# design.net
KiCad netlist of a schematic drawn in Altium Designer
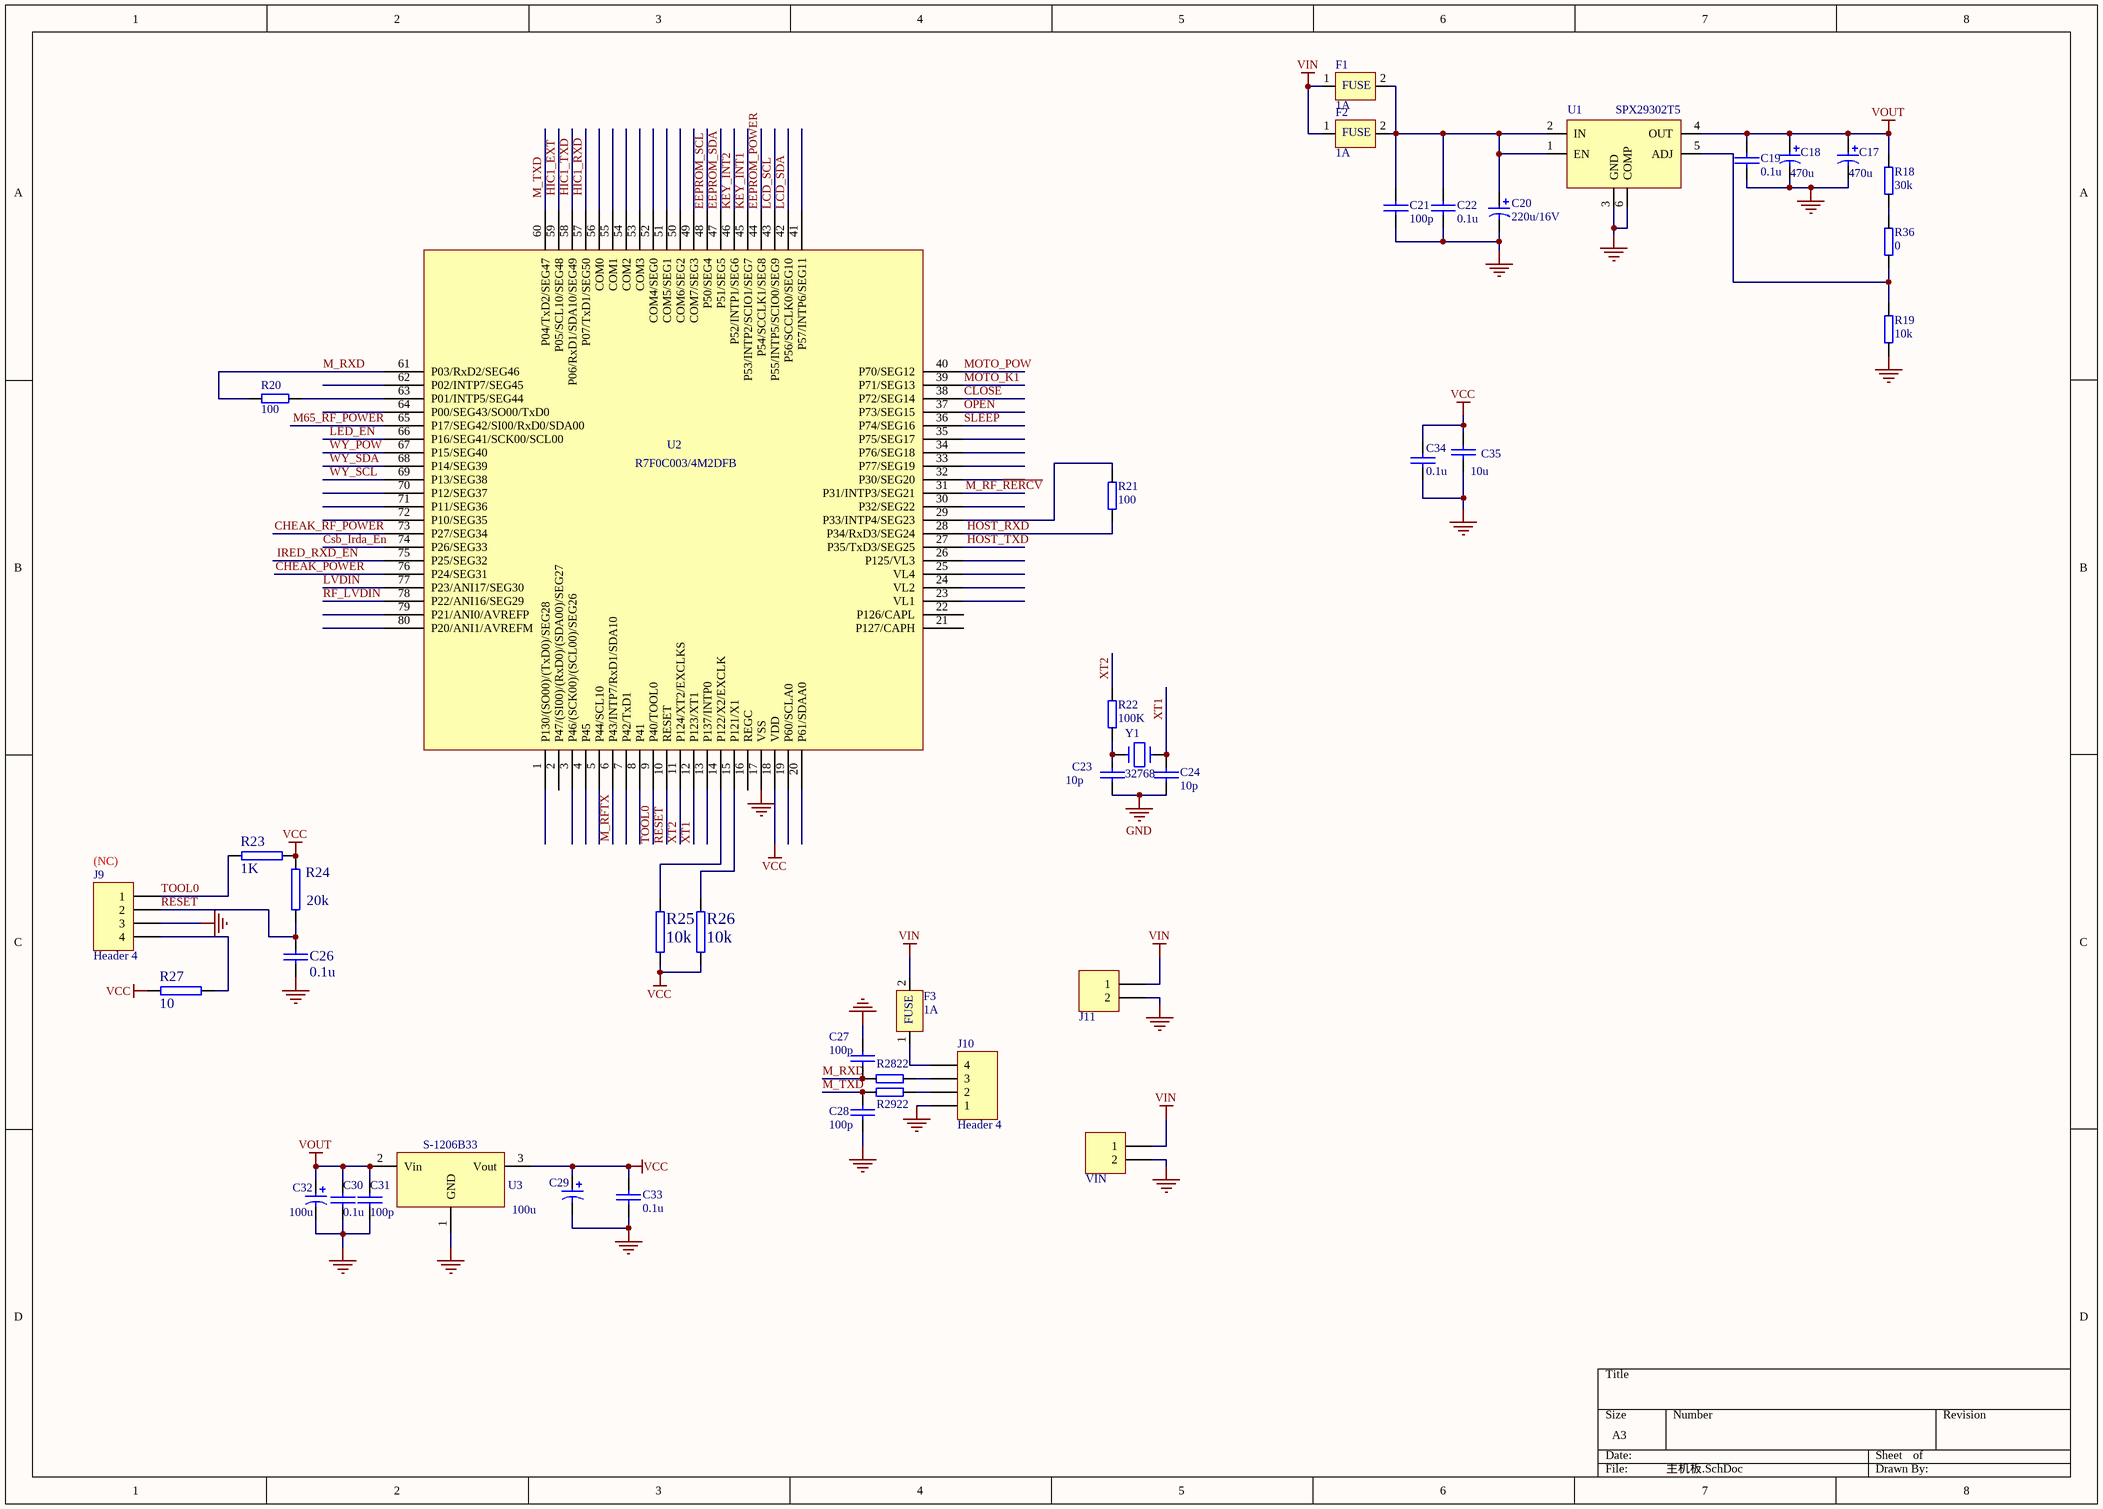
[diagram p0: 主机板.SchDoc]

(export (version "E")
  (design (tool "Eeschema 10.0.6"))
  (components
    (comp (ref "C17")
      (value "470u")
      (footprint "7343")
      (description "钽电容")
      (libsource (lib "CBB_Lib_SCH") (part "CAP-POL2"))
    )
    (comp (ref "C18")
      (value "470u")
      (footprint "7343")
      (description "钽电容")
      (libsource (lib "CBB_Lib_SCH") (part "CAP-POL2"))
    )
    (comp (ref "C19")
      (value "0.1u")
      (footprint "C0603")
      (description "无极性电容")
      (libsource (lib "CBB_Lib_SCH") (part "CAP"))
    )
    (comp (ref "C20")
      (value "220u/16V")
      (footprint "7343")
      (description "钽电容")
      (libsource (lib "CBB_Lib_SCH") (part "CAP-POL2"))
    )
    (comp (ref "C21")
      (value "100p")
      (footprint "C0603")
      (description "无极性电容")
      (libsource (lib "CBB_Lib_SCH") (part "CAP"))
    )
    (comp (ref "C22")
      (value "0.1u")
      (footprint "C0603")
      (description "无极性电容")
      (libsource (lib "CBB_Lib_SCH") (part "CAP"))
    )
    (comp (ref "C23") (value "10p") (footprint "c0603") (libsource (lib "SCH_LIB_WX") (part "CAP1")))
    (comp (ref "C24") (value "10p") (footprint "c0603") (libsource (lib "SCH_LIB_WX") (part "CAP1")))
    (comp (ref "C26")
      (value "0.1u")
      (footprint "C0603")
      (description "Capacitor")
      (libsource (lib "*") (part "CAP"))
    )
    (comp (ref "C27")
      (value "100p")
      (footprint "C0603")
      (description "无极性电容")
      (libsource (lib "CBB_Lib_SCH") (part "CAP"))
    )
    (comp (ref "C28")
      (value "100p")
      (footprint "C0603")
      (description "无极性电容")
      (libsource (lib "CBB_Lib_SCH") (part "CAP"))
    )
    (comp (ref "C29")
      (value "100u")
      (footprint "3528")
      (description "钽电容")
      (libsource (lib "CBB_Lib_SCH") (part "CAP-POL2"))
    )
    (comp (ref "C30")
      (value "0.1u")
      (footprint "C0603")
      (description "无极性电容")
      (libsource (lib "CBB_Lib_SCH") (part "CAP"))
    )
    (comp (ref "C31")
      (value "100p")
      (footprint "C0603")
      (description "无极性电容")
      (libsource (lib "CBB_Lib_SCH") (part "CAP"))
    )
    (comp (ref "C32")
      (value "100u")
      (footprint "3528")
      (description "钽电容")
      (libsource (lib "CBB_Lib_SCH") (part "CAP-POL2"))
    )
    (comp (ref "C33")
      (value "0.1u")
      (footprint "C0603")
      (description "无极性电容")
      (libsource (lib "CBB_Lib_SCH") (part "CAP"))
    )
    (comp (ref "C34")
      (value "0.1u")
      (footprint "C0603")
      (description "无极性电容")
      (libsource (lib "CBB_Lib_SCH") (part "CAP"))
    )
    (comp (ref "C35")
      (value "10u")
      (footprint "C0603")
      (description "无极性电容")
      (libsource (lib "CBB_Lib_SCH") (part "CAP"))
    )
    (comp (ref "F1") (value "1A") (footprint "R1206") (libsource (lib "chip") (part "FUSE")))
    (comp (ref "F2") (value "1A") (footprint "R1206") (libsource (lib "chip") (part "FUSE")))
    (comp (ref "F3") (value "1A") (footprint "R1206") (libsource (lib "") (part "FUSE_1")))
    (comp (ref "J9")
      (value "Header 4")
      (footprint "HDR1X4")
      (description "Header, 4-Pin")
      (fields (field (name "PUBLISHER") "Altium Limited"))
      (libsource (lib "Miscellaneous Connectors") (part "Header 4"))
    )
    (comp (ref "J10")
      (value "Header 4")
      (footprint "HDX4-2.54")
      (description "Header, 4-Pin")
      (fields (field (name "PUBLISHER") "Altium Limited"))
      (libsource (lib "") (part "Header 4_1"))
    )
    (comp (ref "J11")
      (value "Header 2")
      (footprint "SMT2-2.0")
      (description "Header, 2-Pin")
      (libsource (lib "CBB_Lib_SCH") (part "Header 2"))
    )
    (comp (ref "R18") (value "30k") (footprint "R0603") (libsource (lib "CBB_Lib_SCH") (part "RES")))
    (comp (ref "R19") (value "10k") (footprint "R0603") (libsource (lib "CBB_Lib_SCH") (part "RES")))
    (comp (ref "R20") (value "100") (footprint "r0603") (libsource (lib "SCH_LIB_WX") (part "RES")))
    (comp (ref "R21") (value "100") (footprint "R0603") (libsource (lib "Devices") (part "RES")))
    (comp (ref "R22") (value "100K") (footprint "r0603") (libsource (lib "SCH_LIB_WX") (part "RES")))
    (comp (ref "R23") (value "1K") (footprint "R0603") (libsource (lib "*") (part "RES11")))
    (comp (ref "R24") (value "20k") (footprint "R0603") (libsource (lib "*") (part "RES11")))
    (comp (ref "R25") (value "10k") (footprint "r0603") (libsource (lib "PCB_Project1_1") (part "RES2")))
    (comp (ref "R26") (value "10k") (footprint "r0603") (libsource (lib "PCB_Project1_1") (part "RES2")))
    (comp (ref "R27") (value "10") (footprint "R0603") (libsource (lib "*") (part "RES11")))
    (comp (ref "R28") (value "22") (footprint "R0603") (libsource (lib "CBB_Lib_SCH") (part "RES")))
    (comp (ref "R29") (value "22") (footprint "R0603") (libsource (lib "CBB_Lib_SCH") (part "RES")))
    (comp (ref "R36") (value "0") (footprint "R0603") (libsource (lib "CBB_Lib_SCH") (part "RES")))
    (comp (ref "U1")
      (value "SPX29302T5")
      (footprint "TO-263-5")
      (fields (field (name "PUBLISHER") "Altium Limited"))
      (libsource (lib "SCH_LIB_WX") (part "SPX29302T5"))
    )
    (comp (ref "U2")
      (value "R7F0C003/4M2DFB")
      (footprint "MSP437QFP80")
      (libsource (lib "Schlib1") (part "R7F0C003/4M2DFB"))
    )
    (comp (ref "U3") (value "S-1206B33") (footprint "SOT-89") (libsource (lib "*") (part "VOLTRER1")))
    (comp (ref "VIN")
      (value "Header 2")
      (footprint "BATFOOT")
      (description "Header, 2-Pin")
      (libsource (lib "CBB_Lib_SCH") (part "Header 2"))
    )
    (comp (ref "Y1")
      (value "32768")
      (footprint "XTAL-2S")
      (description "晶振,2PIN")
      (libsource (lib "CBB_Lib_SCH") (part "XTAL1"))
    )
  )
  (nets
    (net (code "1") (name "/CHEAK_POWER") (class "Default")
      (node (ref "U2") (pin "76") (pinfunction "P24/SEG31_76") (pintype "passive"))
    )
    (net (code "2") (name "/CHEAK_RF_POWER") (class "Default")
      (node (ref "U2") (pin "73") (pinfunction "P27/SEG34_73") (pintype "passive"))
    )
    (net (code "3") (name "/CLOSE") (class "Default")
      (node (ref "U2") (pin "38") (pinfunction "P72/SEG14_38") (pintype "passive"))
    )
    (net (code "4") (name "/Csb_Irda_En") (class "Default")
      (node (ref "U2") (pin "74") (pinfunction "P26/SEG33_74") (pintype "passive"))
    )
    (net (code "5") (name "/EEPROM_POWER") (class "Default")
      (node (ref "U2") (pin "44") (pinfunction "P54/SCCLK1/SEG8_44") (pintype "passive"))
    )
    (net (code "6") (name "/EEPROM_SCL") (class "Default")
      (node (ref "U2") (pin "48") (pinfunction "P50/SEG4_48") (pintype "passive"))
    )
    (net (code "7") (name "/EEPROM_SDA") (class "Default")
      (node (ref "U2") (pin "47") (pinfunction "P51/SEG5_47") (pintype "passive"))
    )
    (net (code "8") (name "/HIC1_EXT") (class "Default")
      (node (ref "U2") (pin "59") (pinfunction "P05/SCL10/SEG48_59") (pintype "passive"))
    )
    (net (code "9") (name "/HIC1_RXD") (class "Default")
      (node (ref "U2") (pin "57") (pinfunction "P07/TxD1/SEG50_57") (pintype "passive"))
    )
    (net (code "10") (name "/HIC1_TXD") (class "Default")
      (node (ref "U2") (pin "58") (pinfunction "P06/RxD1/SDA10/SEG49_58") (pintype "passive"))
    )
    (net (code "11") (name "/HOST_RXD") (class "Default")
      (node (ref "R21") (pin "1") (pintype "passive"))
      (node (ref "U2") (pin "28") (pinfunction "P34/RxD3/SEG24_28") (pintype "passive"))
    )
    (net (code "12") (name "/HOST_TXD") (class "Default")
      (node (ref "U2") (pin "27") (pinfunction "P35/TxD3/SEG25_27") (pintype "passive"))
    )
    (net (code "13") (name "/IRED_RXD_EN") (class "Default")
      (node (ref "U2") (pin "75") (pinfunction "P25/SEG32_75") (pintype "passive"))
    )
    (net (code "14") (name "/KEY_INT1") (class "Default")
      (node (ref "U2") (pin "45") (pinfunction "P53/INTP2/SCIO1/SEG7_45") (pintype "passive"))
    )
    (net (code "15") (name "/KEY_INT2") (class "Default")
      (node (ref "U2") (pin "46") (pinfunction "P52/INTP1/SEG6_46") (pintype "passive"))
    )
    (net (code "16") (name "/LCD_SCL") (class "Default")
      (node (ref "U2") (pin "43") (pinfunction "P55/INTP5/SCIO0/SEG9_43") (pintype "passive"))
    )
    (net (code "17") (name "/LCD_SDA") (class "Default")
      (node (ref "U2") (pin "42") (pinfunction "P56/SCCLK0/SEG10_42") (pintype "passive"))
    )
    (net (code "18") (name "/LED_EN") (class "Default")
      (node (ref "U2") (pin "66") (pinfunction "P16/SEG41/SCK00/SCL00_66") (pintype "passive"))
    )
    (net (code "19") (name "/LVDIN") (class "Default")
      (node (ref "U2") (pin "77") (pinfunction "P23/ANI17/SEG30_77") (pintype "passive"))
    )
    (net (code "20") (name "/M65_RF_POWER") (class "Default")
      (node (ref "U2") (pin "65") (pinfunction "P17/SEG42/SI00/RxD0/SDA00_65") (pintype "passive"))
    )
    (net (code "21") (name "/MOTO_K1") (class "Default")
      (node (ref "U2") (pin "39") (pinfunction "P71/SEG13_39") (pintype "passive"))
    )
    (net (code "22") (name "/MOTO_POW") (class "Default")
      (node (ref "U2") (pin "40") (pinfunction "P70/SEG12_40") (pintype "passive"))
    )
    (net (code "23") (name "/M_RFTX") (class "Default")
      (node (ref "U2") (pin "6") (pinfunction "P43/INTP7/RxD1/SDA10_6") (pintype "passive"))
    )
    (net (code "24") (name "/M_RF_~{RERCV}") (class "Default")
      (node (ref "U2") (pin "31") (pinfunction "P31/INTP3/SEG21_31") (pintype "passive"))
    )
    (net (code "25") (name "/M_RXD") (class "Default")
      (node (ref "C27") (pin "2") (pintype "passive"))
      (node (ref "R20") (pin "2") (pintype "passive"))
      (node (ref "R28") (pin "1") (pintype "passive"))
      (node (ref "U2") (pin "61") (pinfunction "P03/RxD2/SEG46_61") (pintype "passive"))
    )
    (net (code "26") (name "/M_TXD") (class "Default")
      (node (ref "C28") (pin "2") (pintype "passive"))
      (node (ref "R29") (pin "2") (pintype "passive"))
      (node (ref "U2") (pin "60") (pinfunction "P04/TxD2/SEG47_60") (pintype "passive"))
    )
    (net (code "27") (name "/OPEN") (class "Default")
      (node (ref "U2") (pin "37") (pinfunction "P73/SEG15_37") (pintype "passive"))
    )
    (net (code "28") (name "/RESET") (class "Default")
      (node (ref "C26") (pin "2") (pinfunction "2_2") (pintype "passive"))
      (node (ref "J9") (pin "2") (pinfunction "2_2") (pintype "passive"))
      (node (ref "R24") (pin "2") (pinfunction "2_2") (pintype "passive"))
      (node (ref "U2") (pin "10") (pinfunction "RESET_10") (pintype "passive"))
    )
    (net (code "29") (name "/RF_LVDIN") (class "Default")
      (node (ref "U2") (pin "78") (pinfunction "P22/ANI16/SEG29_78") (pintype "passive"))
    )
    (net (code "30") (name "/SLEEP") (class "Default")
      (node (ref "U2") (pin "36") (pinfunction "P74/SEG16_36") (pintype "passive"))
    )
    (net (code "31") (name "/TOOL0") (class "Default")
      (node (ref "J9") (pin "1") (pinfunction "1_1") (pintype "passive"))
      (node (ref "R23") (pin "1") (pinfunction "1_1") (pintype "passive"))
      (node (ref "U2") (pin "9") (pinfunction "P40/TOOL0_9") (pintype "passive"))
    )
    (net (code "32") (name "/WY_POW") (class "Default")
      (node (ref "U2") (pin "67") (pinfunction "P15/SEG40_67") (pintype "passive"))
    )
    (net (code "33") (name "/WY_SCL") (class "Default")
      (node (ref "U2") (pin "69") (pinfunction "P13/SEG38_69") (pintype "passive"))
    )
    (net (code "34") (name "/WY_SDA") (class "Default")
      (node (ref "U2") (pin "68") (pinfunction "P14/SEG39_68") (pintype "passive"))
    )
    (net (code "35") (name "/XT1") (class "Default")
      (node (ref "C24") (pin "2") (pintype "passive"))
      (node (ref "U2") (pin "12") (pinfunction "P123/XT1_12") (pintype "passive"))
      (node (ref "Y1") (pin "1") (pinfunction "1_1") (pintype "passive"))
    )
    (net (code "36") (name "/XT2") (class "Default")
      (node (ref "R22") (pin "2") (pintype "passive"))
      (node (ref "U2") (pin "11") (pinfunction "P124/XT2/EXCLKS_11") (pintype "passive"))
    )
    (net (code "37") (name "GND") (class "Default")
      (node (ref "C17") (pin "2") (pinfunction "2_2") (pintype "passive"))
      (node (ref "C18") (pin "2") (pinfunction "2_2") (pintype "passive"))
      (node (ref "C19") (pin "1") (pintype "passive"))
      (node (ref "C20") (pin "2") (pinfunction "2_2") (pintype "passive"))
      (node (ref "C21") (pin "1") (pintype "passive"))
      (node (ref "C22") (pin "1") (pintype "passive"))
      (node (ref "C23") (pin "1") (pintype "passive"))
      (node (ref "C24") (pin "1") (pintype "passive"))
      (node (ref "C26") (pin "1") (pinfunction "1_1") (pintype "passive"))
      (node (ref "C27") (pin "1") (pintype "passive"))
      (node (ref "C28") (pin "1") (pintype "passive"))
      (node (ref "C29") (pin "2") (pinfunction "2_2") (pintype "passive"))
      (node (ref "C30") (pin "1") (pintype "passive"))
      (node (ref "C31") (pin "1") (pintype "passive"))
      (node (ref "C32") (pin "2") (pinfunction "2_2") (pintype "passive"))
      (node (ref "C33") (pin "1") (pintype "passive"))
      (node (ref "C34") (pin "2") (pintype "passive"))
      (node (ref "C35") (pin "2") (pintype "passive"))
      (node (ref "J10") (pin "1") (pinfunction "1_1") (pintype "passive"))
      (node (ref "J11") (pin "2") (pinfunction "2_2") (pintype "passive"))
      (node (ref "J9") (pin "3") (pinfunction "3_3") (pintype "passive"))
      (node (ref "R19") (pin "1") (pintype "passive"))
      (node (ref "U1") (pin "3") (pinfunction "GND_3") (pintype "passive"))
      (node (ref "U1") (pin "6") (pinfunction "COMP_6") (pintype "passive"))
      (node (ref "U2") (pin "17") (pinfunction "VSS_17") (pintype "passive"))
      (node (ref "U3") (pin "1") (pinfunction "GND_1") (pintype "passive"))
      (node (ref "VIN") (pin "2") (pinfunction "2_2") (pintype "passive"))
    )
    (net (code "38") (name "Net-(C23-Pad2)") (class "Default")
      (node (ref "C23") (pin "2") (pintype "passive"))
      (node (ref "R22") (pin "1") (pintype "passive"))
      (node (ref "Y1") (pin "2") (pinfunction "2_2") (pintype "passive"))
    )
    (net (code "39") (name "Net-(F3-I-Pad1)") (class "Default")
      (node (ref "F3") (pin "1") (pinfunction "I_1") (pintype "passive"))
      (node (ref "J10") (pin "4") (pinfunction "4_4") (pintype "passive"))
    )
    (net (code "40") (name "Net-(J9-Pad4)") (class "Default")
      (node (ref "J9") (pin "4") (pinfunction "4_4") (pintype "passive"))
      (node (ref "R27") (pin "2") (pinfunction "2_2") (pintype "passive"))
    )
    (net (code "41") (name "Net-(J10-Pad2)") (class "Default")
      (node (ref "J10") (pin "2") (pinfunction "2_2") (pintype "passive"))
      (node (ref "R29") (pin "1") (pintype "passive"))
    )
    (net (code "42") (name "Net-(J10-Pad3)") (class "Default")
      (node (ref "J10") (pin "3") (pinfunction "3_3") (pintype "passive"))
      (node (ref "R28") (pin "2") (pintype "passive"))
    )
    (net (code "43") (name "Net-(R18-Pad1)") (class "Default")
      (node (ref "R18") (pin "1") (pintype "passive"))
      (node (ref "R36") (pin "2") (pintype "passive"))
    )
    (net (code "44") (name "Net-(U1-ADJ)") (class "Default")
      (node (ref "R19") (pin "2") (pintype "passive"))
      (node (ref "R36") (pin "1") (pintype "passive"))
      (node (ref "U1") (pin "5") (pinfunction "ADJ_5") (pintype "passive"))
    )
    (net (code "45") (name "Net-(U1-EN)") (class "Default")
      (node (ref "C20") (pin "1") (pinfunction "1_1") (pintype "passive"))
      (node (ref "C21") (pin "2") (pintype "passive"))
      (node (ref "C22") (pin "2") (pintype "passive"))
      (node (ref "F1") (pin "2") (pinfunction "I_2") (pintype "passive"))
      (node (ref "F2") (pin "2") (pinfunction "I_2") (pintype "passive"))
      (node (ref "U1") (pin "1") (pinfunction "EN_1") (pintype "passive"))
      (node (ref "U1") (pin "2") (pinfunction "IN_2") (pintype "passive"))
    )
    (net (code "46") (name "Net-(U2-P01{slash}INTP5{slash}SEG44)") (class "Default")
      (node (ref "R20") (pin "1") (pintype "passive"))
      (node (ref "U2") (pin "63") (pinfunction "P01/INTP5/SEG44_63") (pintype "passive"))
    )
    (net (code "47") (name "Net-(U2-P33{slash}INTP4{slash}SEG23)") (class "Default")
      (node (ref "R21") (pin "2") (pintype "passive"))
      (node (ref "U2") (pin "29") (pinfunction "P33/INTP4/SEG23_29") (pintype "passive"))
    )
    (net (code "48") (name "Net-(U2-P121{slash}X1)") (class "Default")
      (node (ref "R26") (pin "1") (pinfunction "1_1") (pintype "passive"))
      (node (ref "U2") (pin "15") (pinfunction "P121/X1_15") (pintype "passive"))
    )
    (net (code "49") (name "Net-(U2-P122{slash}X2{slash}EXCLK)") (class "Default")
      (node (ref "R25") (pin "1") (pinfunction "1_1") (pintype "passive"))
      (node (ref "U2") (pin "14") (pinfunction "P122/X2/EXCLK_14") (pintype "passive"))
    )
    (net (code "50") (name "VCC") (class "Default")
      (node (ref "C29") (pin "1") (pinfunction "1_1") (pintype "passive"))
      (node (ref "C33") (pin "2") (pintype "passive"))
      (node (ref "C34") (pin "1") (pintype "passive"))
      (node (ref "C35") (pin "1") (pintype "passive"))
      (node (ref "R23") (pin "2") (pinfunction "2_2") (pintype "passive"))
      (node (ref "R24") (pin "1") (pinfunction "1_1") (pintype "passive"))
      (node (ref "R25") (pin "2") (pinfunction "2_2") (pintype "passive"))
      (node (ref "R26") (pin "2") (pinfunction "2_2") (pintype "passive"))
      (node (ref "R27") (pin "1") (pinfunction "1_1") (pintype "passive"))
      (node (ref "U2") (pin "18") (pinfunction "VDD_18") (pintype "passive"))
      (node (ref "U3") (pin "3") (pinfunction "Vout_3") (pintype "passive"))
    )
    (net (code "51") (name "VIN") (class "Default")
      (node (ref "F1") (pin "1") (pinfunction "I_1") (pintype "passive"))
      (node (ref "F2") (pin "1") (pinfunction "I_1") (pintype "passive"))
      (node (ref "F3") (pin "2") (pinfunction "I_2") (pintype "passive"))
      (node (ref "J11") (pin "1") (pinfunction "1_1") (pintype "passive"))
      (node (ref "VIN") (pin "1") (pinfunction "1_1") (pintype "passive"))
    )
    (net (code "52") (name "VOUT") (class "Default")
      (node (ref "C17") (pin "1") (pinfunction "1_1") (pintype "passive"))
      (node (ref "C18") (pin "1") (pinfunction "1_1") (pintype "passive"))
      (node (ref "C19") (pin "2") (pintype "passive"))
      (node (ref "C30") (pin "2") (pintype "passive"))
      (node (ref "C31") (pin "2") (pintype "passive"))
      (node (ref "C32") (pin "1") (pinfunction "1_1") (pintype "passive"))
      (node (ref "R18") (pin "2") (pintype "passive"))
      (node (ref "U1") (pin "4") (pinfunction "OUT_4") (pintype "passive"))
      (node (ref "U3") (pin "2") (pinfunction "Vin_2") (pintype "passive"))
    )
    (net (code "53") (name "unconnected-(U2-COM0-Pad56)") (class "Default")
      (node (ref "U2") (pin "56") (pinfunction "COM0_56") (pintype "passive"))
    )
    (net (code "54") (name "unconnected-(U2-COM1-Pad55)") (class "Default")
      (node (ref "U2") (pin "55") (pinfunction "COM1_55") (pintype "passive"))
    )
    (net (code "55") (name "unconnected-(U2-COM2-Pad54)") (class "Default")
      (node (ref "U2") (pin "54") (pinfunction "COM2_54") (pintype "passive"))
    )
    (net (code "56") (name "unconnected-(U2-COM3-Pad53)") (class "Default")
      (node (ref "U2") (pin "53") (pinfunction "COM3_53") (pintype "passive"))
    )
    (net (code "57") (name "unconnected-(U2-COM4{slash}SEG0-Pad52)") (class "Default")
      (node (ref "U2") (pin "52") (pinfunction "COM4/SEG0_52") (pintype "passive"))
    )
    (net (code "58") (name "unconnected-(U2-COM5{slash}SEG1-Pad51)") (class "Default")
      (node (ref "U2") (pin "51") (pinfunction "COM5/SEG1_51") (pintype "passive"))
    )
    (net (code "59") (name "unconnected-(U2-COM6{slash}SEG2-Pad50)") (class "Default")
      (node (ref "U2") (pin "50") (pinfunction "COM6/SEG2_50") (pintype "passive"))
    )
    (net (code "60") (name "unconnected-(U2-COM7{slash}SEG3-Pad49)") (class "Default")
      (node (ref "U2") (pin "49") (pinfunction "COM7/SEG3_49") (pintype "passive"))
    )
    (net (code "61") (name "unconnected-(U2-P00{slash}SEG43{slash}SO00{slash}TxD0-Pad64)") (class "Default")
      (node (ref "U2") (pin "64") (pinfunction "P00/SEG43/SO00/TxD0_64") (pintype "passive"))
    )
    (net (code "62") (name "unconnected-(U2-P02{slash}INTP7{slash}SEG45-Pad62)") (class "Default")
      (node (ref "U2") (pin "62") (pinfunction "P02/INTP7/SEG45_62") (pintype "passive"))
    )
    (net (code "63") (name "unconnected-(U2-P10{slash}SEG35-Pad72)") (class "Default")
      (node (ref "U2") (pin "72") (pinfunction "P10/SEG35_72") (pintype "passive"))
    )
    (net (code "64") (name "unconnected-(U2-P11{slash}SEG36-Pad71)") (class "Default")
      (node (ref "U2") (pin "71") (pinfunction "P11/SEG36_71") (pintype "passive"))
    )
    (net (code "65") (name "unconnected-(U2-P12{slash}SEG37-Pad70)") (class "Default")
      (node (ref "U2") (pin "70") (pinfunction "P12/SEG37_70") (pintype "passive"))
    )
    (net (code "66") (name "unconnected-(U2-P20{slash}ANI1{slash}AVREFM-Pad80)") (class "Default")
      (node (ref "U2") (pin "80") (pinfunction "P20/ANI1/AVREFM_80") (pintype "passive"))
    )
    (net (code "67") (name "unconnected-(U2-P21{slash}ANI0{slash}AVREFP-Pad79)") (class "Default")
      (node (ref "U2") (pin "79") (pinfunction "P21/ANI0/AVREFP_79") (pintype "passive"))
    )
    (net (code "68") (name "unconnected-(U2-P30{slash}SEG20-Pad32)") (class "Default")
      (node (ref "U2") (pin "32") (pinfunction "P30/SEG20_32") (pintype "passive"))
    )
    (net (code "69") (name "unconnected-(U2-P32{slash}SEG22-Pad30)") (class "Default")
      (node (ref "U2") (pin "30") (pinfunction "P32/SEG22_30") (pintype "passive"))
    )
    (net (code "70") (name "unconnected-(U2-P41-Pad8)") (class "Default")
      (node (ref "U2") (pin "8") (pinfunction "P41_8") (pintype "passive"))
    )
    (net (code "71") (name "unconnected-(U2-P42{slash}TxD1-Pad7)") (class "Default")
      (node (ref "U2") (pin "7") (pinfunction "P42/TxD1_7") (pintype "passive"))
    )
    (net (code "72") (name "unconnected-(U2-P44{slash}SCL10-Pad5)") (class "Default")
      (node (ref "U2") (pin "5") (pinfunction "P44/SCL10_5") (pintype "passive"))
    )
    (net (code "73") (name "unconnected-(U2-P45-Pad4)") (class "Default")
      (node (ref "U2") (pin "4") (pinfunction "P45_4") (pintype "passive"))
    )
    (net (code "74") (name "unconnected-(U2-P46{slash}(SCK00){slash}(SCL00){slash}SEG26-Pad3)") (class "Default")
      (node (ref "U2") (pin "3") (pinfunction "P46/(SCK00)/(SCL00)/SEG26_3") (pintype "passive"))
    )
    (net (code "75") (name "unconnected-(U2-P47{slash}(SI00){slash}(RxD0){slash}(SDA00){slash}SEG27-Pad2)") (class "Default")
      (node (ref "U2") (pin "2") (pinfunction "P47/(SI00)/(RxD0)/(SDA00)/SEG27_2") (pintype "passive"))
    )
    (net (code "76") (name "unconnected-(U2-P57{slash}INTP6{slash}SEG11-Pad41)") (class "Default")
      (node (ref "U2") (pin "41") (pinfunction "P57/INTP6/SEG11_41") (pintype "passive"))
    )
    (net (code "77") (name "unconnected-(U2-P60{slash}SCLA0-Pad19)") (class "Default")
      (node (ref "U2") (pin "19") (pinfunction "P60/SCLA0_19") (pintype "passive"))
    )
    (net (code "78") (name "unconnected-(U2-P61{slash}SDAA0-Pad20)") (class "Default")
      (node (ref "U2") (pin "20") (pinfunction "P61/SDAA0_20") (pintype "passive"))
    )
    (net (code "79") (name "unconnected-(U2-P75{slash}SEG17-Pad35)") (class "Default")
      (node (ref "U2") (pin "35") (pinfunction "P75/SEG17_35") (pintype "passive"))
    )
    (net (code "80") (name "unconnected-(U2-P76{slash}SEG18-Pad34)") (class "Default")
      (node (ref "U2") (pin "34") (pinfunction "P76/SEG18_34") (pintype "passive"))
    )
    (net (code "81") (name "unconnected-(U2-P77{slash}SEG19-Pad33)") (class "Default")
      (node (ref "U2") (pin "33") (pinfunction "P77/SEG19_33") (pintype "passive"))
    )
    (net (code "82") (name "unconnected-(U2-P125{slash}VL3-Pad26)") (class "Default")
      (node (ref "U2") (pin "26") (pinfunction "P125/VL3_26") (pintype "passive"))
    )
    (net (code "83") (name "unconnected-(U2-P126{slash}CAPL-Pad22)") (class "Default")
      (node (ref "U2") (pin "22") (pinfunction "P126/CAPL_22") (pintype "passive"))
    )
    (net (code "84") (name "unconnected-(U2-P127{slash}CAPH-Pad21)") (class "Default")
      (node (ref "U2") (pin "21") (pinfunction "P127/CAPH_21") (pintype "passive"))
    )
    (net (code "85") (name "unconnected-(U2-P130{slash}(SO00){slash}(TxD0){slash}SEG28-Pad1)") (class "Default")
      (node (ref "U2") (pin "1") (pinfunction "P130/(SO00)/(TxD0)/SEG28_1") (pintype "passive"))
    )
    (net (code "86") (name "unconnected-(U2-P137{slash}INTP0-Pad13)") (class "Default")
      (node (ref "U2") (pin "13") (pinfunction "P137/INTP0_13") (pintype "passive"))
    )
    (net (code "87") (name "unconnected-(U2-REGC-Pad16)") (class "Default")
      (node (ref "U2") (pin "16") (pinfunction "REGC_16") (pintype "passive"))
    )
    (net (code "88") (name "unconnected-(U2-VL1-Pad23)") (class "Default")
      (node (ref "U2") (pin "23") (pinfunction "VL1_23") (pintype "passive"))
    )
    (net (code "89") (name "unconnected-(U2-VL2-Pad24)") (class "Default")
      (node (ref "U2") (pin "24") (pinfunction "VL2_24") (pintype "passive"))
    )
    (net (code "90") (name "unconnected-(U2-VL4-Pad25)") (class "Default")
      (node (ref "U2") (pin "25") (pinfunction "VL4_25") (pintype "passive"))
    )
  )
)
